# isolated_TTL_to_485.net
KiCad netlist of a schematic drawn in Altium Designer
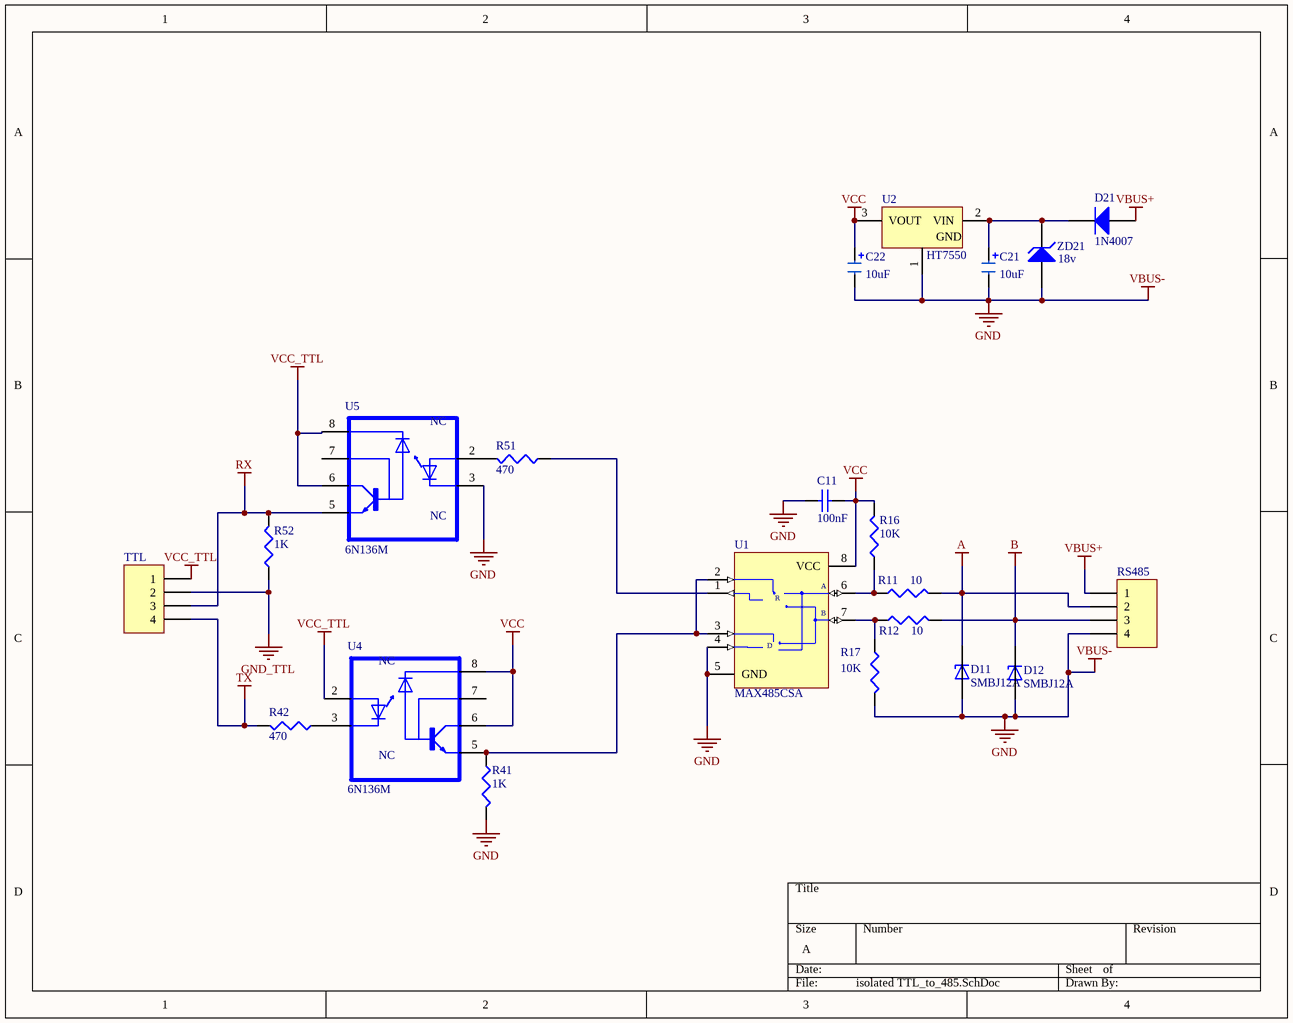
[diagram p0: isolated TTL_to_485.SchDoc]

(export (version "E")
  (design (tool "Eeschema 10.0.6"))
  (components
    (comp (ref "C11")
      (value "100nF")
      (footprint "C1206")
      (description "Capacitor")
      (fields (field (name "Comment") "Cap"))
      (libsource (lib "My PCBs Components") (part "Cap"))
    )
    (comp (ref "C21")
      (value "10uF")
      (footprint "Tantalium CASE B")
      (description "Polarized Capacitor Tantalium")
      (fields (field (name "Comment") "106E"))
      (libsource (lib "My PCBs Components") (part "Cap Pol2"))
    )
    (comp (ref "C22")
      (value "10uF")
      (footprint "Tantalium CASE B")
      (description "Polarized Capacitor Tantalium")
      (fields (field (name "Comment") "106C"))
      (libsource (lib "My PCBs Components") (part "Cap Pol2"))
    )
    (comp (ref "D11")
      (value "SMBJ12A")
      (footprint "DIOM4336X265N")
      (description "15.6V Clamp 17.5A Ipp Tvs Diode Surface Mount DO-214AA (SMB)")
      (fields (field (name "MF") "ON Semiconductor"))
      (libsource (lib "SMBJ12A") (part "SMBJ12A"))
    )
    (comp (ref "D12")
      (value "SMBJ12A")
      (footprint "DIOM4336X265N")
      (description "15.6V Clamp 17.5A Ipp Tvs Diode Surface Mount DO-214AA (SMB)")
      (fields (field (name "MF") "ON Semiconductor"))
      (libsource (lib "SMBJ12A") (part "SMBJ12A"))
    )
    (comp (ref "D21")
      (value "1N4007")
      (footprint "SMA")
      (description "Default Diode")
      (fields (field (name "PUBLISHER") "Altium Limited"))
      (libsource (lib "Miscellaneous Devices") (part "Diode"))
    )
    (comp (ref "R11")
      (value "10")
      (footprint "1206 Resistor")
      (description "Resistor")
      (fields (field (name "Comment") "Res"))
      (libsource (lib "My PCBs Components") (part "Res"))
    )
    (comp (ref "R12")
      (value "10")
      (footprint "1206 Resistor")
      (description "Resistor")
      (fields (field (name "Comment") "Res"))
      (libsource (lib "My PCBs Components") (part "Res"))
    )
    (comp (ref "R16")
      (value "10K")
      (footprint "1206 Resistor")
      (description "Resistor")
      (fields (field (name "Comment") "Res"))
      (libsource (lib "My PCBs Components") (part "Res"))
    )
    (comp (ref "R17")
      (value "10K")
      (footprint "1206 Resistor")
      (description "Resistor")
      (fields (field (name "Comment") "Res"))
      (libsource (lib "My PCBs Components") (part "Res"))
    )
    (comp (ref "R41")
      (value "1K")
      (footprint "1206 Resistor")
      (description "Resistor")
      (fields (field (name "Comment") "Res"))
      (libsource (lib "My PCBs Components") (part "Res"))
    )
    (comp (ref "R42")
      (value "470")
      (footprint "1206 Resistor")
      (description "Resistor")
      (fields (field (name "Comment") "Res"))
      (libsource (lib "My PCBs Components") (part "Res"))
    )
    (comp (ref "R51")
      (value "470")
      (footprint "1206 Resistor")
      (description "Resistor")
      (fields (field (name "Comment") "Res"))
      (libsource (lib "My PCBs Components") (part "Res"))
    )
    (comp (ref "R52")
      (value "1K")
      (footprint "1206 Resistor")
      (description "Resistor")
      (fields (field (name "Comment") "Res"))
      (libsource (lib "My PCBs Components") (part "Res"))
    )
    (comp (ref "RS485")
      (value "Header 4")
      (footprint "HDR1X4")
      (description "Header, 4-Pin")
      (fields (field (name "PUBLISHER") "Altium Limited"))
      (libsource (lib "Miscellaneous Connectors") (part "Header 4"))
    )
    (comp (ref "TTL")
      (value "Header 4")
      (footprint "HDR1X4")
      (description "Header, 4-Pin")
      (fields (field (name "PUBLISHER") "Altium Limited"))
      (libsource (lib "") (part "Header 4_1"))
    )
    (comp (ref "U1")
      (value "MAX485CSA")
      (footprint "NSO8_N")
      (description "Low-Power, Slew-Rate-Limited RS-485/RS-422 Transceiver")
      (fields (field (name "PUBLISHER") "Altium Limited"))
      (libsource (lib "Maxim Communication Transceiver") (part "MAX485CSA"))
    )
    (comp (ref "U2")
      (value "HT7550")
      (footprint "SOT-89_M")
      (description "Positive Voltage Regulator, 3.3V, 4-Pin SOT-89, Tape and Reel")
      (fields (field (name "PARTNUMBER") "L78L33ABUTR"))
      (libsource (lib "STMicroelectronics Power Management Linear Regulator") (part "L78L33ABUTR"))
    )
    (comp (ref "U4")
      (value "6N136M")
      (footprint "DIP762W50P254L977H451Q8")
      (description "High Speed Optocoupler, 1 MBd, Photodiode with Transistor Output")
      (libsource (lib "6N136M") (part "6N136M"))
    )
    (comp (ref "U5")
      (value "6N136M")
      (footprint "DIP762W50P254L977H451Q8")
      (description "High Speed Optocoupler, 1 MBd, Photodiode with Transistor Output")
      (libsource (lib "6N136M") (part "6N136M"))
    )
    (comp (ref "ZD21")
      (value "18v")
      (footprint "Mini MELF")
      (description "Zener Diode")
      (fields (field (name "Comment") "Diode Zener"))
      (libsource (lib "My PCBs Components") (part "Diode Zener"))
    )
  )
  (nets
    (net (code "1") (name "A") (class "Default")
      (node (ref "D11") (pin "C") (pinfunction "C_C") (pintype "passive"))
      (node (ref "R11") (pin "2") (pinfunction "2_2") (pintype "passive"))
      (node (ref "RS485") (pin "2") (pinfunction "2_2") (pintype "passive"))
    )
    (net (code "2") (name "B") (class "Default")
      (node (ref "D12") (pin "C") (pinfunction "C_C") (pintype "passive"))
      (node (ref "R12") (pin "2") (pinfunction "2_2") (pintype "passive"))
      (node (ref "RS485") (pin "3") (pinfunction "3_3") (pintype "passive"))
    )
    (net (code "3") (name "GND") (class "Default")
      (node (ref "C11") (pin "2") (pinfunction "2_2") (pintype "passive"))
      (node (ref "C21") (pin "2") (pintype "passive"))
      (node (ref "C22") (pin "2") (pintype "passive"))
      (node (ref "D11") (pin "A") (pinfunction "A_A") (pintype "passive"))
      (node (ref "D12") (pin "A") (pinfunction "A_A") (pintype "passive"))
      (node (ref "R17") (pin "2") (pinfunction "2_2") (pintype "passive"))
      (node (ref "R41") (pin "2") (pinfunction "2_2") (pintype "passive"))
      (node (ref "RS485") (pin "4") (pinfunction "4_4") (pintype "passive"))
      (node (ref "U1") (pin "4") (pinfunction "DI_4") (pintype "input"))
      (node (ref "U1") (pin "5") (pinfunction "GND_5") (pintype "power_in"))
      (node (ref "U2") (pin "1") (pinfunction "GND_1") (pintype "power_in"))
      (node (ref "U5") (pin "3") (pinfunction "C_3") (pintype "passive"))
      (node (ref "ZD21") (pin "1") (pinfunction "A_1") (pintype "passive"))
    )
    (net (code "4") (name "GND_TTL") (class "Default")
      (node (ref "R52") (pin "1") (pinfunction "1_1") (pintype "passive"))
      (node (ref "TTL") (pin "2") (pinfunction "2_2") (pintype "passive"))
    )
    (net (code "5") (name "Net-(D21-K)") (class "Default")
      (node (ref "C21") (pin "1") (pintype "passive"))
      (node (ref "D21") (pin "2") (pinfunction "K_2") (pintype "passive"))
      (node (ref "U2") (pin "2") (pinfunction "VIN_2") (pintype "power_in"))
      (node (ref "ZD21") (pin "2") (pinfunction "K_2") (pintype "passive"))
    )
    (net (code "6") (name "Net-(U1-A)") (class "Default")
      (node (ref "R11") (pin "1") (pinfunction "1_1") (pintype "passive"))
      (node (ref "R16") (pin "1") (pinfunction "1_1") (pintype "passive"))
      (node (ref "U1") (pin "6") (pinfunction "A_6") (pintype "bidirectional"))
    )
    (net (code "7") (name "Net-(U1-B)") (class "Default")
      (node (ref "R12") (pin "1") (pinfunction "1_1") (pintype "passive"))
      (node (ref "R17") (pin "1") (pinfunction "1_1") (pintype "passive"))
      (node (ref "U1") (pin "7") (pinfunction "B_7") (pintype "bidirectional"))
    )
    (net (code "8") (name "Net-(U1-DE)") (class "Default")
      (node (ref "R41") (pin "1") (pinfunction "1_1") (pintype "passive"))
      (node (ref "U1") (pin "2") (pinfunction "~{RE}_2") (pintype "input"))
      (node (ref "U1") (pin "3") (pinfunction "DE_3") (pintype "input"))
      (node (ref "U4") (pin "5") (pinfunction "E/GND_5") (pintype "passive"))
    )
    (net (code "9") (name "Net-(U1-RO)") (class "Default")
      (node (ref "R51") (pin "1") (pinfunction "1_1") (pintype "passive"))
      (node (ref "U1") (pin "1") (pinfunction "RO_1") (pintype "output"))
    )
    (net (code "10") (name "Net-(U4-C)") (class "Default")
      (node (ref "R42") (pin "1") (pinfunction "1_1") (pintype "passive"))
      (node (ref "U4") (pin "3") (pinfunction "C_3") (pintype "passive"))
    )
    (net (code "11") (name "Net-(U5-A)") (class "Default")
      (node (ref "R51") (pin "2") (pinfunction "2_2") (pintype "passive"))
      (node (ref "U5") (pin "2") (pinfunction "A_2") (pintype "passive"))
    )
    (net (code "12") (name "RX") (class "Default")
      (node (ref "R52") (pin "2") (pinfunction "2_2") (pintype "passive"))
      (node (ref "TTL") (pin "3") (pinfunction "3_3") (pintype "passive"))
      (node (ref "U5") (pin "5") (pinfunction "E/GND_5") (pintype "passive"))
    )
    (net (code "13") (name "TX") (class "Default")
      (node (ref "R42") (pin "2") (pinfunction "2_2") (pintype "passive"))
      (node (ref "TTL") (pin "4") (pinfunction "4_4") (pintype "passive"))
    )
    (net (code "14") (name "VBUS+") (class "Default")
      (node (ref "D21") (pin "1") (pinfunction "A_1") (pintype "passive"))
      (node (ref "RS485") (pin "1") (pinfunction "1_1") (pintype "passive"))
    )
    (net (code "15") (name "VCC") (class "Default")
      (node (ref "C11") (pin "1") (pinfunction "1_1") (pintype "passive"))
      (node (ref "C22") (pin "1") (pintype "passive"))
      (node (ref "R16") (pin "2") (pinfunction "2_2") (pintype "passive"))
      (node (ref "U1") (pin "8") (pinfunction "VCC_8") (pintype "power_in"))
      (node (ref "U2") (pin "3") (pinfunction "VOUT_3") (pintype "power_in"))
      (node (ref "U4") (pin "6") (pinfunction "C/VO_6") (pintype "passive"))
      (node (ref "U4") (pin "8") (pinfunction "C/VCC_8") (pintype "passive"))
    )
    (net (code "16") (name "VCC_TTL") (class "Default")
      (node (ref "TTL") (pin "1") (pinfunction "1_1") (pintype "passive"))
      (node (ref "U4") (pin "2") (pinfunction "A_2") (pintype "passive"))
      (node (ref "U5") (pin "6") (pinfunction "C/VO_6") (pintype "passive"))
      (node (ref "U5") (pin "8") (pinfunction "C/VCC_8") (pintype "passive"))
    )
    (net (code "17") (name "unconnected-(U4-B{slash}VB-Pad7)") (class "Default")
      (node (ref "U4") (pin "7") (pinfunction "B/VB_7") (pintype "passive"))
    )
    (net (code "18") (name "unconnected-(U5-B{slash}VB-Pad7)") (class "Default")
      (node (ref "U5") (pin "7") (pinfunction "B/VB_7") (pintype "passive"))
    )
  )
)
